# Delta_Robot.net
KiCad netlist of a schematic drawn in EAGLE
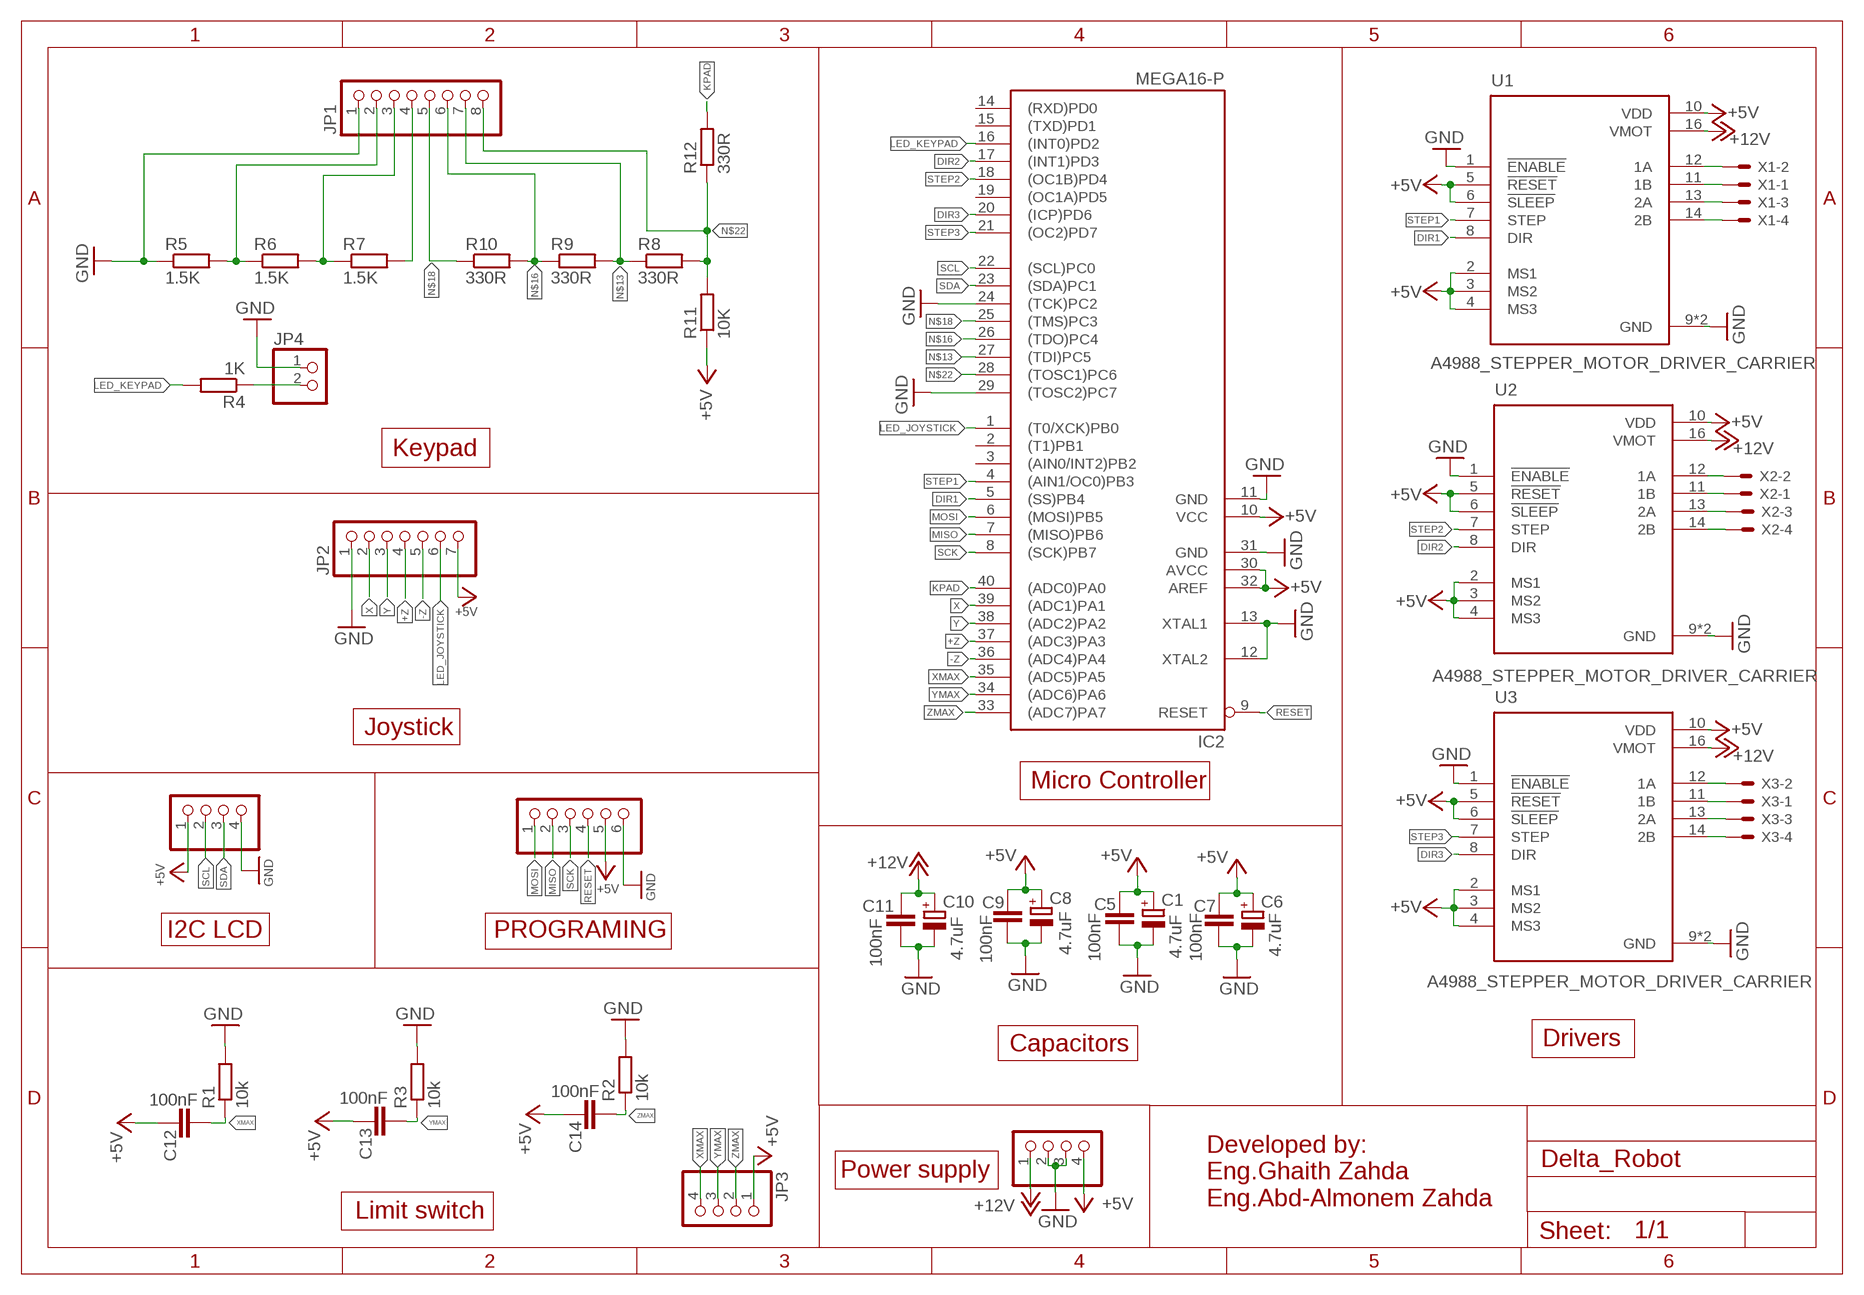
[diagram p0: schematic, sheet 1]

(export (version "E")
  (design (tool "Eeschema 10.0.6"))
  (components
    (comp (ref "C1")
      (value "4.7uF")
      (footprint "eagle-import:E2,5-5")
      (libsource (lib "eagle-import") (part "CPOL-EUE2.5-5"))
    )
    (comp (ref "C5")
      (value "100nF")
      (footprint "eagle-import:C025-024X044")
      (libsource (lib "eagle-import") (part "C-EU025-024X044"))
    )
    (comp (ref "C6")
      (value "4.7uF")
      (footprint "eagle-import:E2,5-5")
      (libsource (lib "eagle-import") (part "CPOL-EUE2.5-5"))
    )
    (comp (ref "C7")
      (value "100nF")
      (footprint "eagle-import:C025-024X044")
      (libsource (lib "eagle-import") (part "C-EU025-024X044"))
    )
    (comp (ref "C8")
      (value "4.7uF")
      (footprint "eagle-import:E2,5-5")
      (libsource (lib "eagle-import") (part "CPOL-EUE2.5-5"))
    )
    (comp (ref "C9")
      (value "100nF")
      (footprint "eagle-import:C025-024X044")
      (libsource (lib "eagle-import") (part "C-EU025-024X044"))
    )
    (comp (ref "C10")
      (value "4.7uF")
      (footprint "eagle-import:E2,5-5")
      (libsource (lib "eagle-import") (part "CPOL-EUE2.5-5"))
    )
    (comp (ref "C11")
      (value "100nF")
      (footprint "eagle-import:C025-024X044")
      (libsource (lib "eagle-import") (part "C-EU025-024X044"))
    )
    (comp (ref "C12")
      (value "100nF")
      (footprint "eagle-import:C025-024X044")
      (libsource (lib "eagle-import") (part "C-EU025-024X044"))
    )
    (comp (ref "C13")
      (value "100nF")
      (footprint "eagle-import:C025-024X044")
      (libsource (lib "eagle-import") (part "C-EU025-024X044"))
    )
    (comp (ref "C14")
      (value "100nF")
      (footprint "eagle-import:C025-024X044")
      (libsource (lib "eagle-import") (part "C-EU025-024X044"))
    )
    (comp (ref "I2C_LCD")
      (value "PINHD-1X4")
      (footprint "eagle-import:1X04")
      (libsource (lib "eagle-import") (part "PINHD-1X4"))
    )
    (comp (ref "IC2")
      (value "MEGA16-P")
      (footprint "eagle-import:DIL40")
      (fields (field (name "MPN") "ATMEGA16-16PU"))
      (libsource (lib "eagle-import") (part "MEGA16-P"))
    )
    (comp (ref "JP1")
      (value "PINHD-1X8")
      (footprint "eagle-import:1X08")
      (libsource (lib "eagle-import") (part "PINHD-1X8"))
    )
    (comp (ref "JP2")
      (value "PINHD-1X7")
      (footprint "eagle-import:1X07")
      (libsource (lib "eagle-import") (part "PINHD-1X7"))
    )
    (comp (ref "JP3")
      (value "PINHD-1X4")
      (footprint "eagle-import:1X04")
      (libsource (lib "eagle-import") (part "PINHD-1X4"))
    )
    (comp (ref "JP4")
      (value "PINHD-1X2")
      (footprint "eagle-import:1X02")
      (libsource (lib "eagle-import") (part "PINHD-1X2"))
    )
    (comp (ref "POWER")
      (value "PINHD-1X4")
      (footprint "eagle-import:1X04")
      (libsource (lib "eagle-import") (part "PINHD-1X4"))
    )
    (comp (ref "PROGRAMING")
      (value "PINHD-1X6")
      (footprint "eagle-import:1X06")
      (libsource (lib "eagle-import") (part "PINHD-1X6"))
    )
    (comp (ref "R1")
      (value "10k")
      (footprint "eagle-import:0204_5")
      (libsource (lib "eagle-import") (part "R-EU_0204/5"))
    )
    (comp (ref "R2")
      (value "10k")
      (footprint "eagle-import:0204_5")
      (libsource (lib "eagle-import") (part "R-EU_0204/5"))
    )
    (comp (ref "R3")
      (value "10k")
      (footprint "eagle-import:0204_5")
      (libsource (lib "eagle-import") (part "R-EU_0204/5"))
    )
    (comp (ref "R4")
      (value "1K")
      (footprint "eagle-import:0204_5")
      (libsource (lib "eagle-import") (part "R-EU_0204/5"))
    )
    (comp (ref "R5")
      (value "1.5K")
      (footprint "eagle-import:0204_5")
      (libsource (lib "eagle-import") (part "R-EU_0204/5"))
    )
    (comp (ref "R6")
      (value "1.5K")
      (footprint "eagle-import:0204_5")
      (libsource (lib "eagle-import") (part "R-EU_0204/5"))
    )
    (comp (ref "R7")
      (value "1.5K")
      (footprint "eagle-import:0204_5")
      (libsource (lib "eagle-import") (part "R-EU_0204/5"))
    )
    (comp (ref "R8")
      (value "330R")
      (footprint "eagle-import:0204_5")
      (libsource (lib "eagle-import") (part "R-EU_0204/5"))
    )
    (comp (ref "R9")
      (value "330R")
      (footprint "eagle-import:0204_5")
      (libsource (lib "eagle-import") (part "R-EU_0204/5"))
    )
    (comp (ref "R10")
      (value "330R")
      (footprint "eagle-import:0204_5")
      (libsource (lib "eagle-import") (part "R-EU_0204/5"))
    )
    (comp (ref "R11")
      (value "10K")
      (footprint "eagle-import:0204_5")
      (libsource (lib "eagle-import") (part "R-EU_0204/5"))
    )
    (comp (ref "R12")
      (value "330R")
      (footprint "eagle-import:0204_5")
      (libsource (lib "eagle-import") (part "R-EU_0204/5"))
    )
    (comp (ref "U1")
      (value "A4988_STEPPER_MOTOR_DRIVER_CARRIER")
      (footprint "eagle-import:MODULE_A4988_STEPPER_MOTOR_DRIVER_CARRIER")
      (fields (field (name "MF") "Pololu") (field (name "MP") "A4988 STEPPER MOTOR DRIVER CARRIER"))
      (libsource (lib "eagle-import") (part "A4988_STEPPER_MOTOR_DRIVER_CARRIER"))
    )
    (comp (ref "U2")
      (value "A4988_STEPPER_MOTOR_DRIVER_CARRIER")
      (footprint "eagle-import:MODULE_A4988_STEPPER_MOTOR_DRIVER_CARRIER")
      (fields (field (name "MF") "Pololu") (field (name "MP") "A4988 STEPPER MOTOR DRIVER CARRIER"))
      (libsource (lib "eagle-import") (part "A4988_STEPPER_MOTOR_DRIVER_CARRIER"))
    )
    (comp (ref "U3")
      (value "A4988_STEPPER_MOTOR_DRIVER_CARRIER")
      (footprint "eagle-import:MODULE_A4988_STEPPER_MOTOR_DRIVER_CARRIER")
      (fields (field (name "MF") "Pololu") (field (name "MP") "A4988 STEPPER MOTOR DRIVER CARRIER"))
      (libsource (lib "eagle-import") (part "A4988_STEPPER_MOTOR_DRIVER_CARRIER"))
    )
    (comp (ref "X1")
      (value "JST-XH-04-PIN-LONG-PAD")
      (footprint "eagle-import:JST-XH-04-PACKAGE-LONG-PAD")
      (libsource (lib "eagle-import") (part "JST-XH-04-PIN-LONG-PAD"))
    )
    (comp (ref "X2")
      (value "JST-XH-04-PIN-LONG-PAD")
      (footprint "eagle-import:JST-XH-04-PACKAGE-LONG-PAD")
      (libsource (lib "eagle-import") (part "JST-XH-04-PIN-LONG-PAD"))
    )
    (comp (ref "X3")
      (value "JST-XH-04-PIN-LONG-PAD")
      (footprint "eagle-import:JST-XH-04-PACKAGE-LONG-PAD")
      (libsource (lib "eagle-import") (part "JST-XH-04-PIN-LONG-PAD"))
    )
  )
  (nets
    (net (code "1") (name "+5V") (class "Default")
      (node (ref "C1") (pin "+") (pinfunction "+_+") (pintype "passive"))
      (node (ref "C12") (pin "2") (pinfunction "2_2") (pintype "passive"))
      (node (ref "C13") (pin "2") (pinfunction "2_2") (pintype "passive"))
      (node (ref "C14") (pin "2") (pinfunction "2_2") (pintype "passive"))
      (node (ref "C5") (pin "2") (pinfunction "2_2") (pintype "passive"))
      (node (ref "C6") (pin "+") (pinfunction "+_+") (pintype "passive"))
      (node (ref "C7") (pin "2") (pinfunction "2_2") (pintype "passive"))
      (node (ref "C8") (pin "+") (pinfunction "+_+") (pintype "passive"))
      (node (ref "C9") (pin "2") (pinfunction "2_2") (pintype "passive"))
      (node (ref "I2C_LCD") (pin "1") (pinfunction "1_1") (pintype "passive"))
      (node (ref "IC2") (pin "10") (pinfunction "VCC_10") (pintype "power_in"))
      (node (ref "IC2") (pin "30") (pinfunction "AVCC_30") (pintype "power_in"))
      (node (ref "IC2") (pin "32") (pinfunction "AREF_32") (pintype "passive"))
      (node (ref "JP2") (pin "7") (pinfunction "7_7") (pintype "passive"))
      (node (ref "JP3") (pin "1") (pinfunction "1_1") (pintype "passive"))
      (node (ref "POWER") (pin "4") (pinfunction "4_4") (pintype "passive"))
      (node (ref "PROGRAMING") (pin "5") (pinfunction "5_5") (pintype "passive"))
      (node (ref "R11") (pin "1") (pinfunction "1_1") (pintype "passive"))
      (node (ref "U1") (pin "10") (pinfunction "VDD_10") (pintype "power_in"))
      (node (ref "U1") (pin "2") (pinfunction "MS1_2") (pintype "input"))
      (node (ref "U1") (pin "3") (pinfunction "MS2_3") (pintype "input"))
      (node (ref "U1") (pin "4") (pinfunction "MS3_4") (pintype "input"))
      (node (ref "U1") (pin "5") (pinfunction "~{RESET}_5") (pintype "input"))
      (node (ref "U1") (pin "6") (pinfunction "~{SLEEP}_6") (pintype "input"))
      (node (ref "U2") (pin "10") (pinfunction "VDD_10") (pintype "power_in"))
      (node (ref "U2") (pin "2") (pinfunction "MS1_2") (pintype "input"))
      (node (ref "U2") (pin "3") (pinfunction "MS2_3") (pintype "input"))
      (node (ref "U2") (pin "4") (pinfunction "MS3_4") (pintype "input"))
      (node (ref "U2") (pin "5") (pinfunction "~{RESET}_5") (pintype "input"))
      (node (ref "U2") (pin "6") (pinfunction "~{SLEEP}_6") (pintype "input"))
      (node (ref "U3") (pin "10") (pinfunction "VDD_10") (pintype "power_in"))
      (node (ref "U3") (pin "2") (pinfunction "MS1_2") (pintype "input"))
      (node (ref "U3") (pin "3") (pinfunction "MS2_3") (pintype "input"))
      (node (ref "U3") (pin "4") (pinfunction "MS3_4") (pintype "input"))
      (node (ref "U3") (pin "5") (pinfunction "~{RESET}_5") (pintype "input"))
      (node (ref "U3") (pin "6") (pinfunction "~{SLEEP}_6") (pintype "input"))
    )
    (net (code "2") (name "+12V") (class "Default")
      (node (ref "C10") (pin "+") (pinfunction "+_+") (pintype "passive"))
      (node (ref "C11") (pin "2") (pinfunction "2_2") (pintype "passive"))
      (node (ref "POWER") (pin "1") (pinfunction "1_1") (pintype "passive"))
      (node (ref "U1") (pin "16") (pinfunction "VMOT_16") (pintype "power_in"))
      (node (ref "U2") (pin "16") (pinfunction "VMOT_16") (pintype "power_in"))
      (node (ref "U3") (pin "16") (pinfunction "VMOT_16") (pintype "power_in"))
    )
    (net (code "3") (name "+Z") (class "Default")
      (node (ref "IC2") (pin "37") (pinfunction "(ADC3)PA3_37") (pintype "bidirectional"))
      (node (ref "JP2") (pin "4") (pinfunction "4_4") (pintype "passive"))
    )
    (net (code "4") (name "-Z") (class "Default")
      (node (ref "IC2") (pin "36") (pinfunction "(ADC4)PA4_36") (pintype "bidirectional"))
      (node (ref "JP2") (pin "5") (pinfunction "5_5") (pintype "passive"))
    )
    (net (code "5") (name "DIR1") (class "Default")
      (node (ref "IC2") (pin "5") (pinfunction "(SS)PB4_5") (pintype "bidirectional"))
      (node (ref "U1") (pin "8") (pinfunction "DIR_8") (pintype "input"))
    )
    (net (code "6") (name "DIR2") (class "Default")
      (node (ref "IC2") (pin "17") (pinfunction "(INT1)PD3_17") (pintype "bidirectional"))
      (node (ref "U2") (pin "8") (pinfunction "DIR_8") (pintype "input"))
    )
    (net (code "7") (name "DIR3") (class "Default")
      (node (ref "IC2") (pin "20") (pinfunction "(ICP)PD6_20") (pintype "bidirectional"))
      (node (ref "U3") (pin "8") (pinfunction "DIR_8") (pintype "input"))
    )
    (net (code "8") (name "GND") (class "Default")
      (node (ref "C1") (pin "-") (pinfunction "-_-") (pintype "passive"))
      (node (ref "C10") (pin "-") (pinfunction "-_-") (pintype "passive"))
      (node (ref "C11") (pin "1") (pinfunction "1_1") (pintype "passive"))
      (node (ref "C5") (pin "1") (pinfunction "1_1") (pintype "passive"))
      (node (ref "C6") (pin "-") (pinfunction "-_-") (pintype "passive"))
      (node (ref "C7") (pin "1") (pinfunction "1_1") (pintype "passive"))
      (node (ref "C8") (pin "-") (pinfunction "-_-") (pintype "passive"))
      (node (ref "C9") (pin "1") (pinfunction "1_1") (pintype "passive"))
      (node (ref "I2C_LCD") (pin "4") (pinfunction "4_4") (pintype "passive"))
      (node (ref "IC2") (pin "11") (pinfunction "GND_11") (pintype "power_in"))
      (node (ref "IC2") (pin "12") (pinfunction "XTAL2_12") (pintype "bidirectional"))
      (node (ref "IC2") (pin "13") (pinfunction "XTAL1_13") (pintype "bidirectional"))
      (node (ref "IC2") (pin "24") (pinfunction "(TCK)PC2_24") (pintype "bidirectional"))
      (node (ref "IC2") (pin "29") (pinfunction "(TOSC2)PC7_29") (pintype "bidirectional"))
      (node (ref "IC2") (pin "31") (pinfunction "GND_31") (pintype "power_in"))
      (node (ref "JP1") (pin "1") (pinfunction "1_1") (pintype "passive"))
      (node (ref "JP2") (pin "1") (pinfunction "1_1") (pintype "passive"))
      (node (ref "JP4") (pin "1") (pinfunction "1_1") (pintype "passive"))
      (node (ref "POWER") (pin "2") (pinfunction "2_2") (pintype "passive"))
      (node (ref "POWER") (pin "3") (pinfunction "3_3") (pintype "passive"))
      (node (ref "PROGRAMING") (pin "6") (pinfunction "6_6") (pintype "passive"))
      (node (ref "R1") (pin "2") (pinfunction "2_2") (pintype "passive"))
      (node (ref "R2") (pin "2") (pinfunction "2_2") (pintype "passive"))
      (node (ref "R3") (pin "2") (pinfunction "2_2") (pintype "passive"))
      (node (ref "R5") (pin "1") (pinfunction "1_1") (pintype "passive"))
      (node (ref "U1") (pin "1") (pinfunction "~{ENABLE}_1") (pintype "input"))
      (node (ref "U1") (pin "15") (pinfunction "GND_15") (pintype "power_in"))
      (node (ref "U1") (pin "9") (pinfunction "GND_9") (pintype "power_in"))
      (node (ref "U2") (pin "1") (pinfunction "~{ENABLE}_1") (pintype "input"))
      (node (ref "U2") (pin "15") (pinfunction "GND_15") (pintype "power_in"))
      (node (ref "U2") (pin "9") (pinfunction "GND_9") (pintype "power_in"))
      (node (ref "U3") (pin "1") (pinfunction "~{ENABLE}_1") (pintype "input"))
      (node (ref "U3") (pin "15") (pinfunction "GND_15") (pintype "power_in"))
      (node (ref "U3") (pin "9") (pinfunction "GND_9") (pintype "power_in"))
    )
    (net (code "9") (name "KPAD") (class "Default")
      (node (ref "IC2") (pin "40") (pinfunction "(ADC0)PA0_40") (pintype "bidirectional"))
      (node (ref "R12") (pin "2") (pinfunction "2_2") (pintype "passive"))
    )
    (net (code "10") (name "LED_JOYSTICK") (class "Default")
      (node (ref "IC2") (pin "1") (pinfunction "(T0/XCK)PB0_1") (pintype "bidirectional"))
      (node (ref "JP2") (pin "6") (pinfunction "6_6") (pintype "passive"))
    )
    (net (code "11") (name "LED_KEYPAD") (class "Default")
      (node (ref "IC2") (pin "16") (pinfunction "(INT0)PD2_16") (pintype "bidirectional"))
      (node (ref "R4") (pin "2") (pinfunction "2_2") (pintype "passive"))
    )
    (net (code "12") (name "MISO") (class "Default")
      (node (ref "IC2") (pin "7") (pinfunction "(MISO)PB6_7") (pintype "bidirectional"))
      (node (ref "PROGRAMING") (pin "2") (pinfunction "2_2") (pintype "passive"))
    )
    (net (code "13") (name "MOSI") (class "Default")
      (node (ref "IC2") (pin "6") (pinfunction "(MOSI)PB5_6") (pintype "bidirectional"))
      (node (ref "PROGRAMING") (pin "1") (pinfunction "1_1") (pintype "passive"))
    )
    (net (code "14") (name "N$13") (class "Default")
      (node (ref "IC2") (pin "27") (pinfunction "(TDI)PC5_27") (pintype "bidirectional"))
      (node (ref "JP1") (pin "7") (pinfunction "7_7") (pintype "passive"))
      (node (ref "R8") (pin "1") (pinfunction "1_1") (pintype "passive"))
      (node (ref "R9") (pin "2") (pinfunction "2_2") (pintype "passive"))
    )
    (net (code "15") (name "N$16") (class "Default")
      (node (ref "IC2") (pin "26") (pinfunction "(TDO)PC4_26") (pintype "bidirectional"))
      (node (ref "JP1") (pin "6") (pinfunction "6_6") (pintype "passive"))
      (node (ref "R10") (pin "2") (pinfunction "2_2") (pintype "passive"))
      (node (ref "R9") (pin "1") (pinfunction "1_1") (pintype "passive"))
    )
    (net (code "16") (name "N$18") (class "Default")
      (node (ref "IC2") (pin "25") (pinfunction "(TMS)PC3_25") (pintype "bidirectional"))
      (node (ref "JP1") (pin "5") (pinfunction "5_5") (pintype "passive"))
      (node (ref "R10") (pin "1") (pinfunction "1_1") (pintype "passive"))
    )
    (net (code "17") (name "N$22") (class "Default")
      (node (ref "IC2") (pin "28") (pinfunction "(TOSC1)PC6_28") (pintype "bidirectional"))
      (node (ref "JP1") (pin "8") (pinfunction "8_8") (pintype "passive"))
      (node (ref "R11") (pin "2") (pinfunction "2_2") (pintype "passive"))
      (node (ref "R12") (pin "1") (pinfunction "1_1") (pintype "passive"))
      (node (ref "R8") (pin "2") (pinfunction "2_2") (pintype "passive"))
    )
    (net (code "18") (name "Net-(JP1-Pad2)") (class "Default")
      (node (ref "JP1") (pin "2") (pinfunction "2_2") (pintype "passive"))
      (node (ref "R5") (pin "2") (pinfunction "2_2") (pintype "passive"))
      (node (ref "R6") (pin "1") (pinfunction "1_1") (pintype "passive"))
    )
    (net (code "19") (name "Net-(JP1-Pad3)") (class "Default")
      (node (ref "JP1") (pin "3") (pinfunction "3_3") (pintype "passive"))
      (node (ref "R6") (pin "2") (pinfunction "2_2") (pintype "passive"))
      (node (ref "R7") (pin "1") (pinfunction "1_1") (pintype "passive"))
    )
    (net (code "20") (name "Net-(JP1-Pad4)") (class "Default")
      (node (ref "JP1") (pin "4") (pinfunction "4_4") (pintype "passive"))
      (node (ref "R7") (pin "2") (pinfunction "2_2") (pintype "passive"))
    )
    (net (code "21") (name "Net-(JP4-Pad2)") (class "Default")
      (node (ref "JP4") (pin "2") (pinfunction "2_2") (pintype "passive"))
      (node (ref "R4") (pin "1") (pinfunction "1_1") (pintype "passive"))
    )
    (net (code "22") (name "Net-(U1-1A)") (class "Default")
      (node (ref "U1") (pin "12") (pinfunction "1A_12") (pintype "output"))
      (node (ref "X1") (pin "2") (pinfunction "S_2") (pintype "passive"))
    )
    (net (code "23") (name "Net-(U1-1B)") (class "Default")
      (node (ref "U1") (pin "11") (pinfunction "1B_11") (pintype "output"))
      (node (ref "X1") (pin "1") (pinfunction "S_1") (pintype "passive"))
    )
    (net (code "24") (name "Net-(U1-2A)") (class "Default")
      (node (ref "U1") (pin "13") (pinfunction "2A_13") (pintype "output"))
      (node (ref "X1") (pin "3") (pinfunction "S_3") (pintype "passive"))
    )
    (net (code "25") (name "Net-(U1-2B)") (class "Default")
      (node (ref "U1") (pin "14") (pinfunction "2B_14") (pintype "output"))
      (node (ref "X1") (pin "4") (pinfunction "S_4") (pintype "passive"))
    )
    (net (code "26") (name "Net-(U2-1A)") (class "Default")
      (node (ref "U2") (pin "12") (pinfunction "1A_12") (pintype "output"))
      (node (ref "X2") (pin "2") (pinfunction "S_2") (pintype "passive"))
    )
    (net (code "27") (name "Net-(U2-1B)") (class "Default")
      (node (ref "U2") (pin "11") (pinfunction "1B_11") (pintype "output"))
      (node (ref "X2") (pin "1") (pinfunction "S_1") (pintype "passive"))
    )
    (net (code "28") (name "Net-(U2-2A)") (class "Default")
      (node (ref "U2") (pin "13") (pinfunction "2A_13") (pintype "output"))
      (node (ref "X2") (pin "3") (pinfunction "S_3") (pintype "passive"))
    )
    (net (code "29") (name "Net-(U2-2B)") (class "Default")
      (node (ref "U2") (pin "14") (pinfunction "2B_14") (pintype "output"))
      (node (ref "X2") (pin "4") (pinfunction "S_4") (pintype "passive"))
    )
    (net (code "30") (name "Net-(U3-1A)") (class "Default")
      (node (ref "U3") (pin "12") (pinfunction "1A_12") (pintype "output"))
      (node (ref "X3") (pin "2") (pinfunction "S_2") (pintype "passive"))
    )
    (net (code "31") (name "Net-(U3-1B)") (class "Default")
      (node (ref "U3") (pin "11") (pinfunction "1B_11") (pintype "output"))
      (node (ref "X3") (pin "1") (pinfunction "S_1") (pintype "passive"))
    )
    (net (code "32") (name "Net-(U3-2A)") (class "Default")
      (node (ref "U3") (pin "13") (pinfunction "2A_13") (pintype "output"))
      (node (ref "X3") (pin "3") (pinfunction "S_3") (pintype "passive"))
    )
    (net (code "33") (name "Net-(U3-2B)") (class "Default")
      (node (ref "U3") (pin "14") (pinfunction "2B_14") (pintype "output"))
      (node (ref "X3") (pin "4") (pinfunction "S_4") (pintype "passive"))
    )
    (net (code "34") (name "RESET") (class "Default")
      (node (ref "IC2") (pin "9") (pinfunction "RESET_9") (pintype "input"))
      (node (ref "PROGRAMING") (pin "4") (pinfunction "4_4") (pintype "passive"))
    )
    (net (code "35") (name "SCK") (class "Default")
      (node (ref "IC2") (pin "8") (pinfunction "(SCK)PB7_8") (pintype "bidirectional"))
      (node (ref "PROGRAMING") (pin "3") (pinfunction "3_3") (pintype "passive"))
    )
    (net (code "36") (name "SCL") (class "Default")
      (node (ref "I2C_LCD") (pin "2") (pinfunction "2_2") (pintype "passive"))
      (node (ref "IC2") (pin "22") (pinfunction "(SCL)PC0_22") (pintype "bidirectional"))
    )
    (net (code "37") (name "SDA") (class "Default")
      (node (ref "I2C_LCD") (pin "3") (pinfunction "3_3") (pintype "passive"))
      (node (ref "IC2") (pin "23") (pinfunction "(SDA)PC1_23") (pintype "bidirectional"))
    )
    (net (code "38") (name "STEP1") (class "Default")
      (node (ref "IC2") (pin "4") (pinfunction "(AIN1/OC0)PB3_4") (pintype "bidirectional"))
      (node (ref "U1") (pin "7") (pinfunction "STEP_7") (pintype "input"))
    )
    (net (code "39") (name "STEP2") (class "Default")
      (node (ref "IC2") (pin "18") (pinfunction "(OC1B)PD4_18") (pintype "bidirectional"))
      (node (ref "U2") (pin "7") (pinfunction "STEP_7") (pintype "input"))
    )
    (net (code "40") (name "STEP3") (class "Default")
      (node (ref "IC2") (pin "21") (pinfunction "(OC2)PD7_21") (pintype "bidirectional"))
      (node (ref "U3") (pin "7") (pinfunction "STEP_7") (pintype "input"))
    )
    (net (code "41") (name "X") (class "Default")
      (node (ref "IC2") (pin "39") (pinfunction "(ADC1)PA1_39") (pintype "bidirectional"))
      (node (ref "JP2") (pin "2") (pinfunction "2_2") (pintype "passive"))
    )
    (net (code "42") (name "XMAX") (class "Default")
      (node (ref "C12") (pin "1") (pinfunction "1_1") (pintype "passive"))
      (node (ref "IC2") (pin "35") (pinfunction "(ADC5)PA5_35") (pintype "bidirectional"))
      (node (ref "JP3") (pin "4") (pinfunction "4_4") (pintype "passive"))
      (node (ref "R1") (pin "1") (pinfunction "1_1") (pintype "passive"))
    )
    (net (code "43") (name "Y") (class "Default")
      (node (ref "IC2") (pin "38") (pinfunction "(ADC2)PA2_38") (pintype "bidirectional"))
      (node (ref "JP2") (pin "3") (pinfunction "3_3") (pintype "passive"))
    )
    (net (code "44") (name "YMAX") (class "Default")
      (node (ref "C13") (pin "1") (pinfunction "1_1") (pintype "passive"))
      (node (ref "IC2") (pin "34") (pinfunction "(ADC6)PA6_34") (pintype "bidirectional"))
      (node (ref "JP3") (pin "3") (pinfunction "3_3") (pintype "passive"))
      (node (ref "R3") (pin "1") (pinfunction "1_1") (pintype "passive"))
    )
    (net (code "45") (name "ZMAX") (class "Default")
      (node (ref "C14") (pin "1") (pinfunction "1_1") (pintype "passive"))
      (node (ref "IC2") (pin "33") (pinfunction "(ADC7)PA7_33") (pintype "bidirectional"))
      (node (ref "JP3") (pin "2") (pinfunction "2_2") (pintype "passive"))
      (node (ref "R2") (pin "1") (pinfunction "1_1") (pintype "passive"))
    )
    (net (code "46") (name "unconnected-(IC2-(AIN0{slash}INT2)PB2-Pad3)") (class "Default")
      (node (ref "IC2") (pin "3") (pinfunction "(AIN0/INT2)PB2_3") (pintype "bidirectional"))
    )
    (net (code "47") (name "unconnected-(IC2-(OC1A)PD5-Pad19)") (class "Default")
      (node (ref "IC2") (pin "19") (pinfunction "(OC1A)PD5_19") (pintype "bidirectional"))
    )
    (net (code "48") (name "unconnected-(IC2-(RXD)PD0-Pad14)") (class "Default")
      (node (ref "IC2") (pin "14") (pinfunction "(RXD)PD0_14") (pintype "bidirectional"))
    )
    (net (code "49") (name "unconnected-(IC2-(T1)PB1-Pad2)") (class "Default")
      (node (ref "IC2") (pin "2") (pinfunction "(T1)PB1_2") (pintype "bidirectional"))
    )
    (net (code "50") (name "unconnected-(IC2-(TXD)PD1-Pad15)") (class "Default")
      (node (ref "IC2") (pin "15") (pinfunction "(TXD)PD1_15") (pintype "bidirectional"))
    )
  )
)
